# DCU.net
KiCad netlist of a schematic drawn in EAGLE
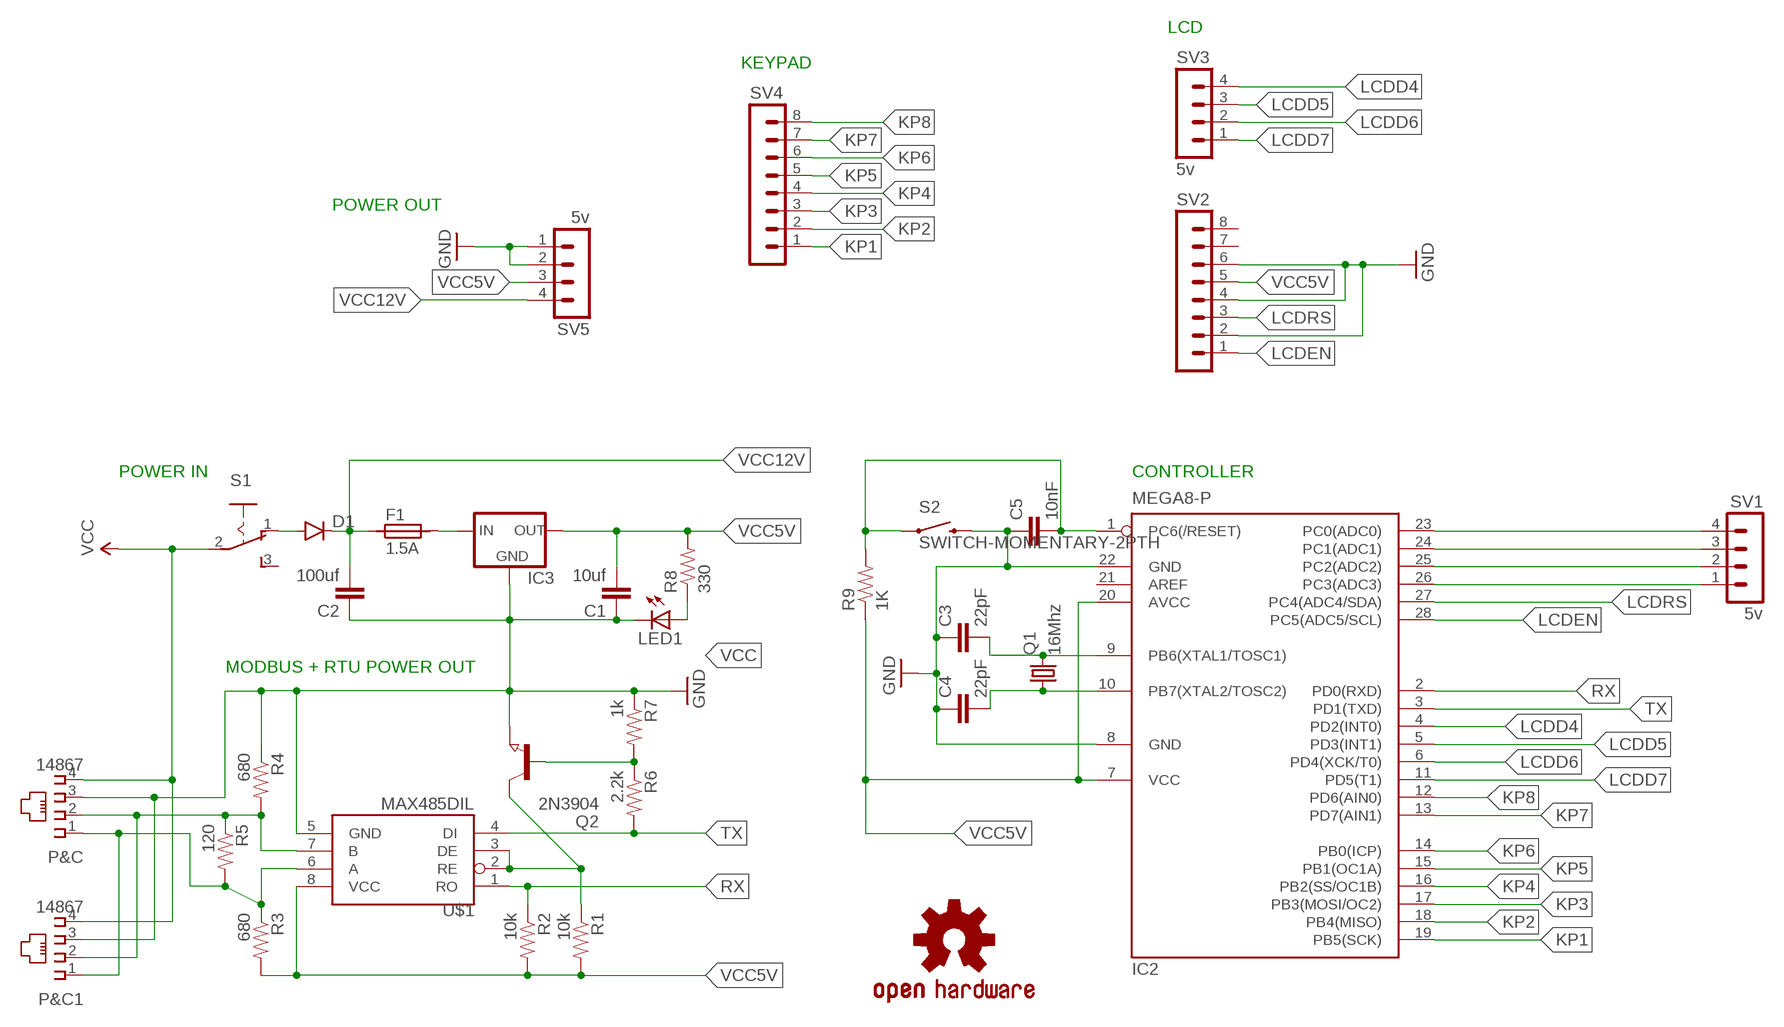
[diagram p0: schematic, sheet 1]

(export (version "E")
  (design (tool "Eeschema 10.0.6"))
  (components
    (comp (ref "C1")
      (value "10uf")
      (footprint "eagle-import:0805")
      (libsource (lib "eagle-import") (part "CAP0805"))
    )
    (comp (ref "C2")
      (value "100uf")
      (footprint "eagle-import:0805")
      (libsource (lib "eagle-import") (part "CAP0805"))
    )
    (comp (ref "C3")
      (value "22pF")
      (footprint "eagle-import:0805")
      (libsource (lib "eagle-import") (part "CAP0805"))
    )
    (comp (ref "C4")
      (value "22pF")
      (footprint "eagle-import:0805")
      (libsource (lib "eagle-import") (part "CAP0805"))
    )
    (comp (ref "C5")
      (value "10nF")
      (footprint "eagle-import:0805")
      (libsource (lib "eagle-import") (part "CAP0805"))
    )
    (comp (ref "D1")
      (value "DIODESMA")
      (footprint "eagle-import:SMA-DIODE")
      (libsource (lib "eagle-import") (part "DIODESMA"))
    )
    (comp (ref "F1")
      (value "1.5A")
      (footprint "eagle-import:1820")
      (libsource (lib "eagle-import") (part "SIBA194600"))
    )
    (comp (ref "IC2")
      (value "MEGA8-P")
      (footprint "eagle-import:DIL28-3")
      (libsource (lib "eagle-import") (part "MEGA8-P"))
    )
    (comp (ref "IC3")
      (value "V_REG_78XX-TO-220")
      (footprint "eagle-import:TO-220-ALT")
      (libsource (lib "eagle-import") (part "V_REG_78XX-TO-220"))
    )
    (comp (ref "LED1")
      (value "LEDCHIP-LED0805")
      (footprint "eagle-import:CHIP-LED0805")
      (libsource (lib "eagle-import") (part "LEDCHIP-LED0805"))
    )
    (comp (ref "LOGO1")
      (value "OSHW-LOGOL")
      (footprint "eagle-import:OSHW-LOGO-L")
      (libsource (lib "eagle-import") (part "OSHW-LOGOL"))
    )
    (comp (ref "P&C")
      (value "14867")
      (footprint "eagle-import:14867")
      (libsource (lib "eagle-import") (part "14867"))
    )
    (comp (ref "P&C1")
      (value "14867")
      (footprint "eagle-import:14867")
      (libsource (lib "eagle-import") (part "14867"))
    )
    (comp (ref "Q1")
      (value "16Mhz")
      (footprint "eagle-import:SM49")
      (libsource (lib "eagle-import") (part "CRYSTALSM49"))
    )
    (comp (ref "Q2")
      (value "2N3904")
      (footprint "eagle-import:SOT23")
      (libsource (lib "eagle-import") (part "NPN-TRANSISTOR_SOT23"))
    )
    (comp (ref "R1")
      (value "10k")
      (footprint "eagle-import:0805")
      (libsource (lib "eagle-import") (part "RESISTOR0805-RES"))
    )
    (comp (ref "R2")
      (value "10k")
      (footprint "eagle-import:0805")
      (libsource (lib "eagle-import") (part "RESISTOR0805-RES"))
    )
    (comp (ref "R3")
      (value "680")
      (footprint "eagle-import:0805")
      (libsource (lib "eagle-import") (part "RESISTOR0805-RES"))
    )
    (comp (ref "R4")
      (value "680")
      (footprint "eagle-import:0805")
      (libsource (lib "eagle-import") (part "RESISTOR0805-RES"))
    )
    (comp (ref "R5")
      (value "120")
      (footprint "eagle-import:0805")
      (libsource (lib "eagle-import") (part "RESISTOR0805-RES"))
    )
    (comp (ref "R6")
      (value "2.2k")
      (footprint "eagle-import:0805")
      (libsource (lib "eagle-import") (part "RESISTOR0805-RES"))
    )
    (comp (ref "R7")
      (value "1k")
      (footprint "eagle-import:0805")
      (libsource (lib "eagle-import") (part "RESISTOR0805-RES"))
    )
    (comp (ref "R8")
      (value "330")
      (footprint "eagle-import:0805")
      (libsource (lib "eagle-import") (part "RESISTOR0805-RES"))
    )
    (comp (ref "R9")
      (value "1K")
      (footprint "eagle-import:0805")
      (libsource (lib "eagle-import") (part "RESISTOR0805-RES"))
    )
    (comp (ref "S1")
      (value "255SB")
      (footprint "eagle-import:255SB")
      (libsource (lib "eagle-import") (part "255SB"))
    )
    (comp (ref "S2")
      (value "SWITCH-MOMENTARY-2PTH")
      (footprint "eagle-import:TACTILE-PTH")
      (libsource (lib "eagle-import") (part "SWITCH-MOMENTARY-2PTH"))
    )
    (comp (ref "SV1")
      (value "5v")
      (footprint "eagle-import:MA04-1")
      (libsource (lib "eagle-import") (part "MA04-1"))
    )
    (comp (ref "SV2")
      (value "MA08-1")
      (footprint "eagle-import:MA08-1")
      (libsource (lib "eagle-import") (part "MA08-1"))
    )
    (comp (ref "SV3")
      (value "5v")
      (footprint "eagle-import:MA04-1")
      (libsource (lib "eagle-import") (part "MA04-1"))
    )
    (comp (ref "SV4")
      (value "MA08-1")
      (footprint "eagle-import:MA08-1")
      (libsource (lib "eagle-import") (part "MA08-1"))
    )
    (comp (ref "SV5")
      (value "5v")
      (footprint "eagle-import:MA04-1")
      (libsource (lib "eagle-import") (part "MA04-1"))
    )
    (comp (ref "U$1")
      (value "MAX485DIL")
      (footprint "eagle-import:DIL08")
      (libsource (lib "eagle-import") (part "MAX485DIL"))
    )
  )
  (nets
    (net (code "1") (name "GND") (class "Default")
      (node (ref "C1") (pin "1") (pinfunction "1_1") (pintype "passive"))
      (node (ref "C2") (pin "1") (pinfunction "1_1") (pintype "passive"))
      (node (ref "C3") (pin "1") (pinfunction "1_1") (pintype "passive"))
      (node (ref "C4") (pin "1") (pinfunction "1_1") (pintype "passive"))
      (node (ref "C5") (pin "1") (pinfunction "1_1") (pintype "passive"))
      (node (ref "IC2") (pin "22") (pinfunction "GND_22") (pintype "power_in"))
      (node (ref "IC2") (pin "8") (pinfunction "GND_8") (pintype "power_in"))
      (node (ref "IC3") (pin "GND") (pinfunction "GND_GND") (pintype "input"))
      (node (ref "LED1") (pin "C") (pinfunction "C_C") (pintype "passive"))
      (node (ref "P&C") (pin "3") (pinfunction "3_3") (pintype "passive"))
      (node (ref "P&C1") (pin "3") (pinfunction "3_3") (pintype "passive"))
      (node (ref "Q2") (pin "2") (pinfunction "E_2") (pintype "passive"))
      (node (ref "R4") (pin "1") (pinfunction "1_1") (pintype "passive"))
      (node (ref "R7") (pin "1") (pinfunction "1_1") (pintype "passive"))
      (node (ref "S2") (pin "3") (pinfunction "2_3") (pintype "passive"))
      (node (ref "SV2") (pin "2") (pinfunction "2_2") (pintype "passive"))
      (node (ref "SV2") (pin "4") (pinfunction "4_4") (pintype "passive"))
      (node (ref "SV2") (pin "6") (pinfunction "6_6") (pintype "passive"))
      (node (ref "SV5") (pin "1") (pinfunction "1_1") (pintype "passive"))
      (node (ref "SV5") (pin "2") (pinfunction "2_2") (pintype "passive"))
      (node (ref "U$1") (pin "5") (pinfunction "GND_5") (pintype "bidirectional"))
    )
    (net (code "2") (name "KP1") (class "Default")
      (node (ref "IC2") (pin "19") (pinfunction "PB5(SCK)_19") (pintype "bidirectional"))
      (node (ref "SV4") (pin "1") (pinfunction "1_1") (pintype "passive"))
    )
    (net (code "3") (name "KP2") (class "Default")
      (node (ref "IC2") (pin "18") (pinfunction "PB4(MISO)_18") (pintype "bidirectional"))
      (node (ref "SV4") (pin "2") (pinfunction "2_2") (pintype "passive"))
    )
    (net (code "4") (name "KP3") (class "Default")
      (node (ref "IC2") (pin "17") (pinfunction "PB3(MOSI/OC2)_17") (pintype "bidirectional"))
      (node (ref "SV4") (pin "3") (pinfunction "3_3") (pintype "passive"))
    )
    (net (code "5") (name "KP4") (class "Default")
      (node (ref "IC2") (pin "16") (pinfunction "PB2(SS/OC1B)_16") (pintype "bidirectional"))
      (node (ref "SV4") (pin "4") (pinfunction "4_4") (pintype "passive"))
    )
    (net (code "6") (name "KP5") (class "Default")
      (node (ref "IC2") (pin "15") (pinfunction "PB1(OC1A)_15") (pintype "bidirectional"))
      (node (ref "SV4") (pin "5") (pinfunction "5_5") (pintype "passive"))
    )
    (net (code "7") (name "KP6") (class "Default")
      (node (ref "IC2") (pin "14") (pinfunction "PB0(ICP)_14") (pintype "bidirectional"))
      (node (ref "SV4") (pin "6") (pinfunction "6_6") (pintype "passive"))
    )
    (net (code "8") (name "KP7") (class "Default")
      (node (ref "IC2") (pin "13") (pinfunction "PD7(AIN1)_13") (pintype "bidirectional"))
      (node (ref "SV4") (pin "7") (pinfunction "7_7") (pintype "passive"))
    )
    (net (code "9") (name "KP8") (class "Default")
      (node (ref "IC2") (pin "12") (pinfunction "PD6(AIN0)_12") (pintype "bidirectional"))
      (node (ref "SV4") (pin "8") (pinfunction "8_8") (pintype "passive"))
    )
    (net (code "10") (name "LCDD4") (class "Default")
      (node (ref "IC2") (pin "4") (pinfunction "PD2(INT0)_4") (pintype "bidirectional"))
      (node (ref "SV3") (pin "4") (pinfunction "4_4") (pintype "passive"))
    )
    (net (code "11") (name "LCDD5") (class "Default")
      (node (ref "IC2") (pin "5") (pinfunction "PD3(INT1)_5") (pintype "bidirectional"))
      (node (ref "SV3") (pin "3") (pinfunction "3_3") (pintype "passive"))
    )
    (net (code "12") (name "LCDD6") (class "Default")
      (node (ref "IC2") (pin "6") (pinfunction "PD4(XCK/T0)_6") (pintype "bidirectional"))
      (node (ref "SV3") (pin "2") (pinfunction "2_2") (pintype "passive"))
    )
    (net (code "13") (name "LCDD7") (class "Default")
      (node (ref "IC2") (pin "11") (pinfunction "PD5(T1)_11") (pintype "bidirectional"))
      (node (ref "SV3") (pin "1") (pinfunction "1_1") (pintype "passive"))
    )
    (net (code "14") (name "LCDEN") (class "Default")
      (node (ref "IC2") (pin "28") (pinfunction "PC5(ADC5/SCL)_28") (pintype "bidirectional"))
      (node (ref "SV2") (pin "1") (pinfunction "1_1") (pintype "passive"))
    )
    (net (code "15") (name "LCDRS") (class "Default")
      (node (ref "IC2") (pin "27") (pinfunction "PC4(ADC4/SDA)_27") (pintype "bidirectional"))
      (node (ref "SV2") (pin "3") (pinfunction "3_3") (pintype "passive"))
    )
    (net (code "16") (name "Net-(F1-Pad2)") (class "Default")
      (node (ref "F1") (pin "2") (pinfunction "2_2") (pintype "passive"))
      (node (ref "IC3") (pin "IN") (pinfunction "IN_IN") (pintype "input"))
    )
    (net (code "17") (name "Net-(IC2-PB6(XTAL1{slash}TOSC1))") (class "Default")
      (node (ref "C3") (pin "2") (pinfunction "2_2") (pintype "passive"))
      (node (ref "IC2") (pin "9") (pinfunction "PB6(XTAL1/TOSC1)_9") (pintype "bidirectional"))
      (node (ref "Q1") (pin "2") (pinfunction "2_2") (pintype "passive"))
    )
    (net (code "18") (name "Net-(IC2-PB7(XTAL2{slash}TOSC2))") (class "Default")
      (node (ref "C4") (pin "2") (pinfunction "2_2") (pintype "passive"))
      (node (ref "IC2") (pin "10") (pinfunction "PB7(XTAL2/TOSC2)_10") (pintype "bidirectional"))
      (node (ref "Q1") (pin "1") (pinfunction "1_1") (pintype "passive"))
    )
    (net (code "19") (name "Net-(IC2-PC0(ADC0))") (class "Default")
      (node (ref "IC2") (pin "23") (pinfunction "PC0(ADC0)_23") (pintype "bidirectional"))
      (node (ref "SV1") (pin "4") (pinfunction "4_4") (pintype "passive"))
    )
    (net (code "20") (name "Net-(IC2-PC1(ADC1))") (class "Default")
      (node (ref "IC2") (pin "24") (pinfunction "PC1(ADC1)_24") (pintype "bidirectional"))
      (node (ref "SV1") (pin "3") (pinfunction "3_3") (pintype "passive"))
    )
    (net (code "21") (name "Net-(IC2-PC2(ADC2))") (class "Default")
      (node (ref "IC2") (pin "25") (pinfunction "PC2(ADC2)_25") (pintype "bidirectional"))
      (node (ref "SV1") (pin "2") (pinfunction "2_2") (pintype "passive"))
    )
    (net (code "22") (name "Net-(IC2-PC3(ADC3))") (class "Default")
      (node (ref "IC2") (pin "26") (pinfunction "PC3(ADC3)_26") (pintype "bidirectional"))
      (node (ref "SV1") (pin "1") (pinfunction "1_1") (pintype "passive"))
    )
    (net (code "23") (name "Net-(IC2-PC6({slash}RESET))") (class "Default")
      (node (ref "C5") (pin "2") (pinfunction "2_2") (pintype "passive"))
      (node (ref "IC2") (pin "1") (pinfunction "PC6(/RESET)_1") (pintype "bidirectional"))
      (node (ref "R9") (pin "2") (pinfunction "2_2") (pintype "passive"))
      (node (ref "S2") (pin "1") (pinfunction "1_1") (pintype "passive"))
    )
    (net (code "24") (name "Net-(LED1-PadA)") (class "Default")
      (node (ref "LED1") (pin "A") (pinfunction "A_A") (pintype "passive"))
      (node (ref "R8") (pin "1") (pinfunction "1_1") (pintype "passive"))
    )
    (net (code "25") (name "Net-(Q2-B)") (class "Default")
      (node (ref "Q2") (pin "1") (pinfunction "B_1") (pintype "passive"))
      (node (ref "R6") (pin "1") (pinfunction "1_1") (pintype "passive"))
      (node (ref "R7") (pin "2") (pinfunction "2_2") (pintype "passive"))
    )
    (net (code "26") (name "Net-(Q2-C)") (class "Default")
      (node (ref "Q2") (pin "3") (pinfunction "C_3") (pintype "passive"))
      (node (ref "R1") (pin "1") (pinfunction "1_1") (pintype "passive"))
      (node (ref "U$1") (pin "2") (pinfunction "RE_2") (pintype "bidirectional"))
      (node (ref "U$1") (pin "3") (pinfunction "DE_3") (pintype "bidirectional"))
    )
    (net (code "27") (name "Net-(S1-O)") (class "Default")
      (node (ref "D1") (pin "A") (pinfunction "A_A") (pintype "passive"))
      (node (ref "S1") (pin "1") (pinfunction "O_1") (pintype "passive"))
    )
    (net (code "28") (name "Net-(U$1-A)") (class "Default")
      (node (ref "P&C") (pin "1") (pinfunction "1_1") (pintype "passive"))
      (node (ref "P&C1") (pin "1") (pinfunction "1_1") (pintype "passive"))
      (node (ref "R3") (pin "1") (pinfunction "1_1") (pintype "passive"))
      (node (ref "R5") (pin "2") (pinfunction "2_2") (pintype "passive"))
      (node (ref "U$1") (pin "6") (pinfunction "A_6") (pintype "bidirectional"))
    )
    (net (code "29") (name "Net-(U$1-B)") (class "Default")
      (node (ref "P&C") (pin "2") (pinfunction "2_2") (pintype "passive"))
      (node (ref "P&C1") (pin "2") (pinfunction "2_2") (pintype "passive"))
      (node (ref "R4") (pin "2") (pinfunction "2_2") (pintype "passive"))
      (node (ref "R5") (pin "1") (pinfunction "1_1") (pintype "passive"))
      (node (ref "U$1") (pin "7") (pinfunction "B_7") (pintype "bidirectional"))
    )
    (net (code "30") (name "RX") (class "Default")
      (node (ref "IC2") (pin "2") (pinfunction "PD0(RXD)_2") (pintype "bidirectional"))
      (node (ref "R2") (pin "1") (pinfunction "1_1") (pintype "passive"))
      (node (ref "U$1") (pin "1") (pinfunction "RO_1") (pintype "bidirectional"))
    )
    (net (code "31") (name "TX") (class "Default")
      (node (ref "IC2") (pin "3") (pinfunction "PD1(TXD)_3") (pintype "bidirectional"))
      (node (ref "R6") (pin "2") (pinfunction "2_2") (pintype "passive"))
      (node (ref "U$1") (pin "4") (pinfunction "DI_4") (pintype "bidirectional"))
    )
    (net (code "32") (name "VCC") (class "Default")
      (node (ref "P&C") (pin "4") (pinfunction "4_4") (pintype "passive"))
      (node (ref "P&C1") (pin "4") (pinfunction "4_4") (pintype "passive"))
      (node (ref "S1") (pin "2") (pinfunction "P_2") (pintype "passive"))
    )
    (net (code "33") (name "VCC5V") (class "Default")
      (node (ref "C1") (pin "2") (pinfunction "2_2") (pintype "passive"))
      (node (ref "IC2") (pin "20") (pinfunction "AVCC_20") (pintype "power_in"))
      (node (ref "IC2") (pin "7") (pinfunction "VCC_7") (pintype "power_in"))
      (node (ref "IC3") (pin "OUT") (pinfunction "OUT_OUT") (pintype "output"))
      (node (ref "R1") (pin "2") (pinfunction "2_2") (pintype "passive"))
      (node (ref "R2") (pin "2") (pinfunction "2_2") (pintype "passive"))
      (node (ref "R3") (pin "2") (pinfunction "2_2") (pintype "passive"))
      (node (ref "R8") (pin "2") (pinfunction "2_2") (pintype "passive"))
      (node (ref "R9") (pin "1") (pinfunction "1_1") (pintype "passive"))
      (node (ref "SV2") (pin "5") (pinfunction "5_5") (pintype "passive"))
      (node (ref "SV5") (pin "3") (pinfunction "3_3") (pintype "passive"))
      (node (ref "U$1") (pin "8") (pinfunction "VCC_8") (pintype "bidirectional"))
    )
    (net (code "34") (name "VCC12V") (class "Default")
      (node (ref "C2") (pin "2") (pinfunction "2_2") (pintype "passive"))
      (node (ref "D1") (pin "C") (pinfunction "C_C") (pintype "passive"))
      (node (ref "F1") (pin "1") (pinfunction "1_1") (pintype "passive"))
      (node (ref "SV5") (pin "4") (pinfunction "4_4") (pintype "passive"))
    )
    (net (code "35") (name "unconnected-(IC2-AREF-Pad21)") (class "Default")
      (node (ref "IC2") (pin "21") (pinfunction "AREF_21") (pintype "passive"))
    )
    (net (code "36") (name "unconnected-(S1-S-Pad3)") (class "Default")
      (node (ref "S1") (pin "3") (pinfunction "S_3") (pintype "passive"))
    )
    (net (code "37") (name "unconnected-(SV2-Pad7)") (class "Default")
      (node (ref "SV2") (pin "7") (pinfunction "7_7") (pintype "passive"))
    )
    (net (code "38") (name "unconnected-(SV2-Pad8)") (class "Default")
      (node (ref "SV2") (pin "8") (pinfunction "8_8") (pintype "passive"))
    )
  )
)
